# DSP_Power.net
KiCad netlist of a schematic drawn in Altium Designer
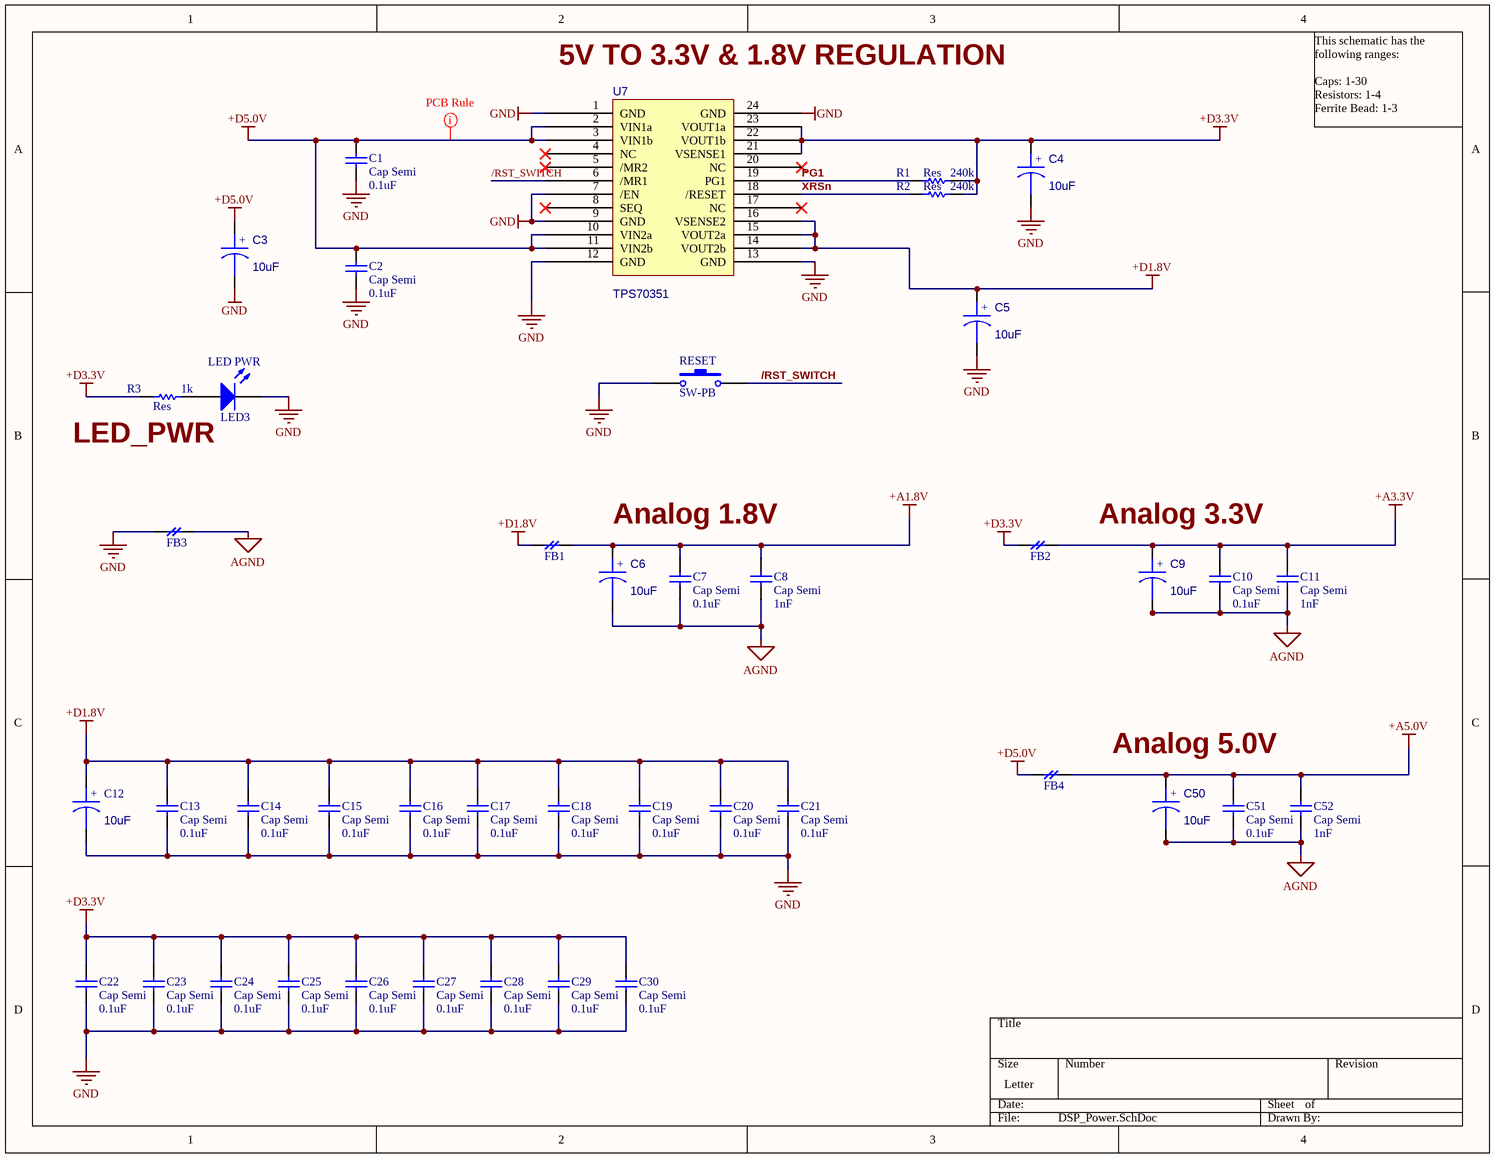
[diagram p0: DSP_Power.SchDoc]

(export (version "E")
  (design (tool "Eeschema 10.0.6"))
  (components
    (comp (ref "C1")
      (value "Cap Semi")
      (footprint "0805")
      (description "Capacitor (Semiconductor SIM Model)")
      (fields (field (name "ALTIUM_VALUE") "0.1uF") (field (name "PUBLISHER") "Altium Limited"))
      (libsource (lib "Miscellaneous Devices") (part "Cap Semi"))
    )
    (comp (ref "C2")
      (value "Cap Semi")
      (footprint "0805")
      (description "Capacitor (Semiconductor SIM Model)")
      (fields (field (name "ALTIUM_VALUE") "0.1uF") (field (name "PUBLISHER") "Altium Limited"))
      (libsource (lib "Miscellaneous Devices") (part "Cap Semi"))
    )
    (comp (ref "C3")
      (value "10uF")
      (footprint "3528")
      (description "digi-399-1563-1-ND")
      (libsource (lib "*") (part "CAPACITOR POL"))
    )
    (comp (ref "C4")
      (value "10uF")
      (footprint "3528")
      (description "digi-399-3096-1-ND")
      (libsource (lib "*") (part "CAPACITOR POL"))
    )
    (comp (ref "C5")
      (value "10uF")
      (footprint "3528")
      (description "digi-399-1576-1-ND")
      (libsource (lib "*") (part "CAPACITOR POL"))
    )
    (comp (ref "C6")
      (value "10uF")
      (footprint "3528")
      (description "digi-399-3096-1-ND")
      (libsource (lib "*") (part "CAPACITOR POL"))
    )
    (comp (ref "C7")
      (value "Cap Semi")
      (footprint "0805")
      (description "Capacitor (Semiconductor SIM Model)")
      (fields (field (name "ALTIUM_VALUE") "0.1uF") (field (name "PUBLISHER") "Altium Limited"))
      (libsource (lib "Miscellaneous Devices") (part "Cap Semi"))
    )
    (comp (ref "C8")
      (value "Cap Semi")
      (footprint "0805")
      (description "Capacitor (Semiconductor SIM Model)")
      (fields (field (name "ALTIUM_VALUE") "1nF") (field (name "PUBLISHER") "Altium Limited"))
      (libsource (lib "Miscellaneous Devices") (part "Cap Semi"))
    )
    (comp (ref "C9")
      (value "10uF")
      (footprint "3528")
      (description "digi-399-3096-1-ND")
      (libsource (lib "*") (part "CAPACITOR POL"))
    )
    (comp (ref "C10")
      (value "Cap Semi")
      (footprint "0805")
      (description "Capacitor (Semiconductor SIM Model)")
      (fields (field (name "ALTIUM_VALUE") "0.1uF") (field (name "PUBLISHER") "Altium Limited"))
      (libsource (lib "Miscellaneous Devices") (part "Cap Semi"))
    )
    (comp (ref "C11")
      (value "Cap Semi")
      (footprint "0805")
      (description "Capacitor (Semiconductor SIM Model)")
      (fields (field (name "ALTIUM_VALUE") "1nF") (field (name "PUBLISHER") "Altium Limited"))
      (libsource (lib "Miscellaneous Devices") (part "Cap Semi"))
    )
    (comp (ref "C12")
      (value "10uF")
      (footprint "3528")
      (description "digi-399-1576-1-ND")
      (libsource (lib "*") (part "CAPACITOR POL"))
    )
    (comp (ref "C13")
      (value "Cap Semi")
      (footprint "0805")
      (description "Capacitor (Semiconductor SIM Model)")
      (fields (field (name "ALTIUM_VALUE") "0.1uF") (field (name "PUBLISHER") "Altium Limited"))
      (libsource (lib "Miscellaneous Devices") (part "Cap Semi"))
    )
    (comp (ref "C14")
      (value "Cap Semi")
      (footprint "0805")
      (description "Capacitor (Semiconductor SIM Model)")
      (fields (field (name "ALTIUM_VALUE") "0.1uF") (field (name "PUBLISHER") "Altium Limited"))
      (libsource (lib "Miscellaneous Devices") (part "Cap Semi"))
    )
    (comp (ref "C15")
      (value "Cap Semi")
      (footprint "0805")
      (description "Capacitor (Semiconductor SIM Model)")
      (fields (field (name "ALTIUM_VALUE") "0.1uF") (field (name "PUBLISHER") "Altium Limited"))
      (libsource (lib "Miscellaneous Devices") (part "Cap Semi"))
    )
    (comp (ref "C16")
      (value "Cap Semi")
      (footprint "0805")
      (description "Capacitor (Semiconductor SIM Model)")
      (fields (field (name "ALTIUM_VALUE") "0.1uF") (field (name "PUBLISHER") "Altium Limited"))
      (libsource (lib "Miscellaneous Devices") (part "Cap Semi"))
    )
    (comp (ref "C17")
      (value "Cap Semi")
      (footprint "0805")
      (description "Capacitor (Semiconductor SIM Model)")
      (fields (field (name "ALTIUM_VALUE") "0.1uF") (field (name "PUBLISHER") "Altium Limited"))
      (libsource (lib "Miscellaneous Devices") (part "Cap Semi"))
    )
    (comp (ref "C18")
      (value "Cap Semi")
      (footprint "0805")
      (description "Capacitor (Semiconductor SIM Model)")
      (fields (field (name "ALTIUM_VALUE") "0.1uF") (field (name "PUBLISHER") "Altium Limited"))
      (libsource (lib "Miscellaneous Devices") (part "Cap Semi"))
    )
    (comp (ref "C19")
      (value "Cap Semi")
      (footprint "0805")
      (description "Capacitor (Semiconductor SIM Model)")
      (fields (field (name "ALTIUM_VALUE") "0.1uF") (field (name "PUBLISHER") "Altium Limited"))
      (libsource (lib "Miscellaneous Devices") (part "Cap Semi"))
    )
    (comp (ref "C20")
      (value "Cap Semi")
      (footprint "0805")
      (description "Capacitor (Semiconductor SIM Model)")
      (fields (field (name "ALTIUM_VALUE") "0.1uF") (field (name "PUBLISHER") "Altium Limited"))
      (libsource (lib "Miscellaneous Devices") (part "Cap Semi"))
    )
    (comp (ref "C21")
      (value "Cap Semi")
      (footprint "0805")
      (description "Capacitor (Semiconductor SIM Model)")
      (fields (field (name "ALTIUM_VALUE") "0.1uF") (field (name "PUBLISHER") "Altium Limited"))
      (libsource (lib "Miscellaneous Devices") (part "Cap Semi"))
    )
    (comp (ref "C22")
      (value "Cap Semi")
      (footprint "0805")
      (description "Capacitor (Semiconductor SIM Model)")
      (fields (field (name "ALTIUM_VALUE") "0.1uF") (field (name "PUBLISHER") "Altium Limited"))
      (libsource (lib "Miscellaneous Devices") (part "Cap Semi"))
    )
    (comp (ref "C23")
      (value "Cap Semi")
      (footprint "0805")
      (description "Capacitor (Semiconductor SIM Model)")
      (fields (field (name "ALTIUM_VALUE") "0.1uF") (field (name "PUBLISHER") "Altium Limited"))
      (libsource (lib "Miscellaneous Devices") (part "Cap Semi"))
    )
    (comp (ref "C24")
      (value "Cap Semi")
      (footprint "0805")
      (description "Capacitor (Semiconductor SIM Model)")
      (fields (field (name "ALTIUM_VALUE") "0.1uF") (field (name "PUBLISHER") "Altium Limited"))
      (libsource (lib "Miscellaneous Devices") (part "Cap Semi"))
    )
    (comp (ref "C25")
      (value "Cap Semi")
      (footprint "0805")
      (description "Capacitor (Semiconductor SIM Model)")
      (fields (field (name "ALTIUM_VALUE") "0.1uF") (field (name "PUBLISHER") "Altium Limited"))
      (libsource (lib "Miscellaneous Devices") (part "Cap Semi"))
    )
    (comp (ref "C26")
      (value "Cap Semi")
      (footprint "0805")
      (description "Capacitor (Semiconductor SIM Model)")
      (fields (field (name "ALTIUM_VALUE") "0.1uF") (field (name "PUBLISHER") "Altium Limited"))
      (libsource (lib "Miscellaneous Devices") (part "Cap Semi"))
    )
    (comp (ref "C27")
      (value "Cap Semi")
      (footprint "0805")
      (description "Capacitor (Semiconductor SIM Model)")
      (fields (field (name "ALTIUM_VALUE") "0.1uF") (field (name "PUBLISHER") "Altium Limited"))
      (libsource (lib "Miscellaneous Devices") (part "Cap Semi"))
    )
    (comp (ref "C28")
      (value "Cap Semi")
      (footprint "0805")
      (description "Capacitor (Semiconductor SIM Model)")
      (fields (field (name "ALTIUM_VALUE") "0.1uF") (field (name "PUBLISHER") "Altium Limited"))
      (libsource (lib "Miscellaneous Devices") (part "Cap Semi"))
    )
    (comp (ref "C29")
      (value "Cap Semi")
      (footprint "0805")
      (description "Capacitor (Semiconductor SIM Model)")
      (fields (field (name "ALTIUM_VALUE") "0.1uF") (field (name "PUBLISHER") "Altium Limited"))
      (libsource (lib "Miscellaneous Devices") (part "Cap Semi"))
    )
    (comp (ref "C30")
      (value "Cap Semi")
      (footprint "0805")
      (description "Capacitor (Semiconductor SIM Model)")
      (fields (field (name "ALTIUM_VALUE") "0.1uF") (field (name "PUBLISHER") "Altium Limited"))
      (libsource (lib "Miscellaneous Devices") (part "Cap Semi"))
    )
    (comp (ref "C50")
      (value "10uF")
      (footprint "3528")
      (description "digi-399-3096-1-ND")
      (libsource (lib "*") (part "CAPACITOR POL"))
    )
    (comp (ref "C51")
      (value "Cap Semi")
      (footprint "0805")
      (description "Capacitor (Semiconductor SIM Model)")
      (fields (field (name "ALTIUM_VALUE") "0.1uF") (field (name "PUBLISHER") "Altium Limited"))
      (libsource (lib "Miscellaneous Devices") (part "Cap Semi"))
    )
    (comp (ref "C52")
      (value "Cap Semi")
      (footprint "0805")
      (description "Capacitor (Semiconductor SIM Model)")
      (fields (field (name "ALTIUM_VALUE") "1nF") (field (name "PUBLISHER") "Altium Limited"))
      (libsource (lib "Miscellaneous Devices") (part "Cap Semi"))
    )
    (comp (ref "FB1")
      (value "Ferrite_Bead")
      (footprint "CR2012-0805")
      (description "Ferrite Bead")
      (libsource (lib "addl") (part "Ferrite_Bead"))
    )
    (comp (ref "FB2")
      (value "Ferrite_Bead")
      (footprint "CR2012-0805")
      (description "Ferrite Bead")
      (libsource (lib "addl") (part "Ferrite_Bead"))
    )
    (comp (ref "FB3")
      (value "Ferrite_Bead")
      (footprint "CR2012-0805")
      (description "Ferrite Bead")
      (libsource (lib "addl") (part "Ferrite_Bead"))
    )
    (comp (ref "FB4")
      (value "Ferrite_Bead")
      (footprint "CR2012-0805")
      (description "Ferrite Bead")
      (libsource (lib "addl") (part "Ferrite_Bead"))
    )
    (comp (ref "LED PWR")
      (value "LED3")
      (footprint "0805")
      (description "Typical BLUE SiC LED")
      (fields (field (name "PUBLISHER") "Altium Limited"))
      (libsource (lib "Miscellaneous Devices") (part "LED3"))
    )
    (comp (ref "R1")
      (value "Res")
      (footprint "0805")
      (description "Semiconductor Resistor")
      (fields (field (name "ALTIUM_VALUE") "240k") (field (name "PUBLISHER") "Altium Limited"))
      (libsource (lib "F28335_DSC_Breakout") (part "Res Semi"))
    )
    (comp (ref "R2")
      (value "Res")
      (footprint "0805")
      (description "Semiconductor Resistor")
      (fields (field (name "ALTIUM_VALUE") "240k") (field (name "PUBLISHER") "Altium Limited"))
      (libsource (lib "F28335_DSC_Breakout") (part "Res Semi"))
    )
    (comp (ref "R3")
      (value "Res")
      (footprint "0805")
      (description "Semiconductor Resistor")
      (fields (field (name "ALTIUM_VALUE") "1k") (field (name "PUBLISHER") "Altium Limited"))
      (libsource (lib "F28335_DSC_Breakout") (part "Res Semi"))
    )
    (comp (ref "RESET")
      (value "SW-PB")
      (footprint "SWITCH_2PAD_SMD")
      (description "Switch")
      (fields (field (name "PUBLISHER") "Altium Limited"))
      (libsource (lib "Miscellaneous Devices") (part "SW-PB"))
    )
    (comp (ref "U7")
      (value "TPS70351")
      (footprint "PWP24")
      (description "IC 3.3V/1.8V LDO REG 24-HTSSOP")
      (libsource (lib "F28335_DSC_Breakout") (part "TPS70351"))
    )
  )
  (nets
    (net (code "1") (name "+A1.8V") (class "Default")
      (node (ref "C6") (pin "1") (pinfunction "1_1") (pintype "passive"))
      (node (ref "C7") (pin "2") (pinfunction "2_2") (pintype "passive"))
      (node (ref "C8") (pin "2") (pinfunction "2_2") (pintype "passive"))
      (node (ref "FB1") (pin "2") (pinfunction "2_2") (pintype "passive"))
    )
    (net (code "2") (name "+A3.3V") (class "Default")
      (node (ref "C10") (pin "2") (pinfunction "2_2") (pintype "passive"))
      (node (ref "C11") (pin "2") (pinfunction "2_2") (pintype "passive"))
      (node (ref "C9") (pin "1") (pinfunction "1_1") (pintype "passive"))
      (node (ref "FB2") (pin "2") (pinfunction "2_2") (pintype "passive"))
    )
    (net (code "3") (name "+A5.0V") (class "Default")
      (node (ref "C50") (pin "1") (pinfunction "1_1") (pintype "passive"))
      (node (ref "C51") (pin "2") (pinfunction "2_2") (pintype "passive"))
      (node (ref "C52") (pin "2") (pinfunction "2_2") (pintype "passive"))
      (node (ref "FB4") (pin "2") (pinfunction "2_2") (pintype "passive"))
    )
    (net (code "4") (name "+D1.8V") (class "Default")
      (node (ref "C12") (pin "1") (pinfunction "1_1") (pintype "passive"))
      (node (ref "C13") (pin "2") (pinfunction "2_2") (pintype "passive"))
      (node (ref "C14") (pin "2") (pinfunction "2_2") (pintype "passive"))
      (node (ref "C15") (pin "2") (pinfunction "2_2") (pintype "passive"))
      (node (ref "C16") (pin "2") (pinfunction "2_2") (pintype "passive"))
      (node (ref "C17") (pin "2") (pinfunction "2_2") (pintype "passive"))
      (node (ref "C18") (pin "2") (pinfunction "2_2") (pintype "passive"))
      (node (ref "C19") (pin "2") (pinfunction "2_2") (pintype "passive"))
      (node (ref "C20") (pin "2") (pinfunction "2_2") (pintype "passive"))
      (node (ref "C21") (pin "2") (pinfunction "2_2") (pintype "passive"))
      (node (ref "C5") (pin "1") (pinfunction "1_1") (pintype "passive"))
      (node (ref "FB1") (pin "1") (pinfunction "1_1") (pintype "passive"))
      (node (ref "U7") (pin "14") (pinfunction "VOUT2b_14") (pintype "passive"))
      (node (ref "U7") (pin "15") (pinfunction "VOUT2a_15") (pintype "passive"))
      (node (ref "U7") (pin "16") (pinfunction "VSENSE2_16") (pintype "passive"))
    )
    (net (code "5") (name "+D3.3V") (class "Default")
      (node (ref "C22") (pin "2") (pinfunction "2_2") (pintype "passive"))
      (node (ref "C23") (pin "2") (pinfunction "2_2") (pintype "passive"))
      (node (ref "C24") (pin "2") (pinfunction "2_2") (pintype "passive"))
      (node (ref "C25") (pin "2") (pinfunction "2_2") (pintype "passive"))
      (node (ref "C26") (pin "2") (pinfunction "2_2") (pintype "passive"))
      (node (ref "C27") (pin "2") (pinfunction "2_2") (pintype "passive"))
      (node (ref "C28") (pin "2") (pinfunction "2_2") (pintype "passive"))
      (node (ref "C29") (pin "2") (pinfunction "2_2") (pintype "passive"))
      (node (ref "C30") (pin "2") (pinfunction "2_2") (pintype "passive"))
      (node (ref "C4") (pin "1") (pinfunction "1_1") (pintype "passive"))
      (node (ref "FB2") (pin "1") (pinfunction "1_1") (pintype "passive"))
      (node (ref "R1") (pin "2") (pinfunction "2_2") (pintype "passive"))
      (node (ref "R2") (pin "2") (pinfunction "2_2") (pintype "passive"))
      (node (ref "R3") (pin "1") (pinfunction "1_1") (pintype "passive"))
      (node (ref "U7") (pin "21") (pinfunction "VSENSE1_21") (pintype "passive"))
      (node (ref "U7") (pin "22") (pinfunction "VOUT1b_22") (pintype "passive"))
      (node (ref "U7") (pin "23") (pinfunction "VOUT1a_23") (pintype "passive"))
    )
    (net (code "6") (name "+D5.0V") (class "Default")
      (node (ref "C1") (pin "2") (pinfunction "2_2") (pintype "passive"))
      (node (ref "C2") (pin "2") (pinfunction "2_2") (pintype "passive"))
      (node (ref "C3") (pin "1") (pinfunction "1_1") (pintype "passive"))
      (node (ref "FB4") (pin "1") (pinfunction "1_1") (pintype "passive"))
      (node (ref "U7") (pin "10") (pinfunction "VIN2a_10") (pintype "passive"))
      (node (ref "U7") (pin "11") (pinfunction "VIN2b_11") (pintype "passive"))
      (node (ref "U7") (pin "2") (pinfunction "VIN1a_2") (pintype "passive"))
      (node (ref "U7") (pin "3") (pinfunction "VIN1b_3") (pintype "passive"))
    )
    (net (code "7") (name "/PG1") (class "Default")
      (node (ref "R1") (pin "1") (pinfunction "1_1") (pintype "passive"))
      (node (ref "U7") (pin "19") (pinfunction "PG1_19") (pintype "passive"))
    )
    (net (code "8") (name "/XRSn") (class "Default")
      (node (ref "R2") (pin "1") (pinfunction "1_1") (pintype "passive"))
      (node (ref "U7") (pin "18") (pinfunction "/RESET_18") (pintype "passive"))
    )
    (net (code "9") (name "/{slash}RST_SWITCH") (class "Default")
      (node (ref "RESET") (pin "2") (pinfunction "2_2") (pintype "passive"))
      (node (ref "U7") (pin "6") (pinfunction "/MR1_6") (pintype "passive"))
    )
    (net (code "10") (name "AGND") (class "Default")
      (node (ref "C10") (pin "1") (pinfunction "1_1") (pintype "passive"))
      (node (ref "C11") (pin "1") (pinfunction "1_1") (pintype "passive"))
      (node (ref "C50") (pin "2") (pinfunction "2_2") (pintype "passive"))
      (node (ref "C51") (pin "1") (pinfunction "1_1") (pintype "passive"))
      (node (ref "C52") (pin "1") (pinfunction "1_1") (pintype "passive"))
      (node (ref "C6") (pin "2") (pinfunction "2_2") (pintype "passive"))
      (node (ref "C7") (pin "1") (pinfunction "1_1") (pintype "passive"))
      (node (ref "C8") (pin "1") (pinfunction "1_1") (pintype "passive"))
      (node (ref "C9") (pin "2") (pinfunction "2_2") (pintype "passive"))
      (node (ref "FB3") (pin "2") (pinfunction "2_2") (pintype "passive"))
    )
    (net (code "11") (name "GND") (class "Default")
      (node (ref "C1") (pin "1") (pinfunction "1_1") (pintype "passive"))
      (node (ref "C12") (pin "2") (pinfunction "2_2") (pintype "passive"))
      (node (ref "C13") (pin "1") (pinfunction "1_1") (pintype "passive"))
      (node (ref "C14") (pin "1") (pinfunction "1_1") (pintype "passive"))
      (node (ref "C15") (pin "1") (pinfunction "1_1") (pintype "passive"))
      (node (ref "C16") (pin "1") (pinfunction "1_1") (pintype "passive"))
      (node (ref "C17") (pin "1") (pinfunction "1_1") (pintype "passive"))
      (node (ref "C18") (pin "1") (pinfunction "1_1") (pintype "passive"))
      (node (ref "C19") (pin "1") (pinfunction "1_1") (pintype "passive"))
      (node (ref "C2") (pin "1") (pinfunction "1_1") (pintype "passive"))
      (node (ref "C20") (pin "1") (pinfunction "1_1") (pintype "passive"))
      (node (ref "C21") (pin "1") (pinfunction "1_1") (pintype "passive"))
      (node (ref "C22") (pin "1") (pinfunction "1_1") (pintype "passive"))
      (node (ref "C23") (pin "1") (pinfunction "1_1") (pintype "passive"))
      (node (ref "C24") (pin "1") (pinfunction "1_1") (pintype "passive"))
      (node (ref "C25") (pin "1") (pinfunction "1_1") (pintype "passive"))
      (node (ref "C26") (pin "1") (pinfunction "1_1") (pintype "passive"))
      (node (ref "C27") (pin "1") (pinfunction "1_1") (pintype "passive"))
      (node (ref "C28") (pin "1") (pinfunction "1_1") (pintype "passive"))
      (node (ref "C29") (pin "1") (pinfunction "1_1") (pintype "passive"))
      (node (ref "C3") (pin "2") (pinfunction "2_2") (pintype "passive"))
      (node (ref "C30") (pin "1") (pinfunction "1_1") (pintype "passive"))
      (node (ref "C4") (pin "2") (pinfunction "2_2") (pintype "passive"))
      (node (ref "C5") (pin "2") (pinfunction "2_2") (pintype "passive"))
      (node (ref "FB3") (pin "1") (pinfunction "1_1") (pintype "passive"))
      (node (ref "LED PWR") (pin "2") (pinfunction "K_2") (pintype "passive"))
      (node (ref "RESET") (pin "1") (pinfunction "1_1") (pintype "passive"))
      (node (ref "U7") (pin "1") (pinfunction "GND_1") (pintype "passive"))
      (node (ref "U7") (pin "12") (pinfunction "GND_12") (pintype "passive"))
      (node (ref "U7") (pin "13") (pinfunction "GND_13") (pintype "passive"))
      (node (ref "U7") (pin "24") (pinfunction "GND_24") (pintype "passive"))
      (node (ref "U7") (pin "7") (pinfunction "/EN_7") (pintype "passive"))
      (node (ref "U7") (pin "9") (pinfunction "GND_9") (pintype "passive"))
    )
    (net (code "12") (name "Net-(LED PWR-A)") (class "Default")
      (node (ref "LED PWR") (pin "1") (pinfunction "A_1") (pintype "passive"))
      (node (ref "R3") (pin "2") (pinfunction "2_2") (pintype "passive"))
    )
    (net (code "13") (name "unconnected-(U7-NC-Pad4)") (class "Default")
      (node (ref "U7") (pin "4") (pinfunction "NC_4") (pintype "passive+no_connect"))
    )
    (net (code "14") (name "unconnected-(U7-NC-Pad17)") (class "Default")
      (node (ref "U7") (pin "17") (pinfunction "NC_17") (pintype "passive+no_connect"))
    )
    (net (code "15") (name "unconnected-(U7-NC-Pad20)") (class "Default")
      (node (ref "U7") (pin "20") (pinfunction "NC_20") (pintype "passive+no_connect"))
    )
    (net (code "16") (name "unconnected-(U7-SEQ-Pad8)") (class "Default")
      (node (ref "U7") (pin "8") (pinfunction "SEQ_8") (pintype "passive+no_connect"))
    )
    (net (code "17") (name "unconnected-(U7-{slash}MR2-Pad5)") (class "Default")
      (node (ref "U7") (pin "5") (pinfunction "/MR2_5") (pintype "passive+no_connect"))
    )
  )
)
